# Schematic.net
KiCad netlist of a schematic drawn in Altium Designer
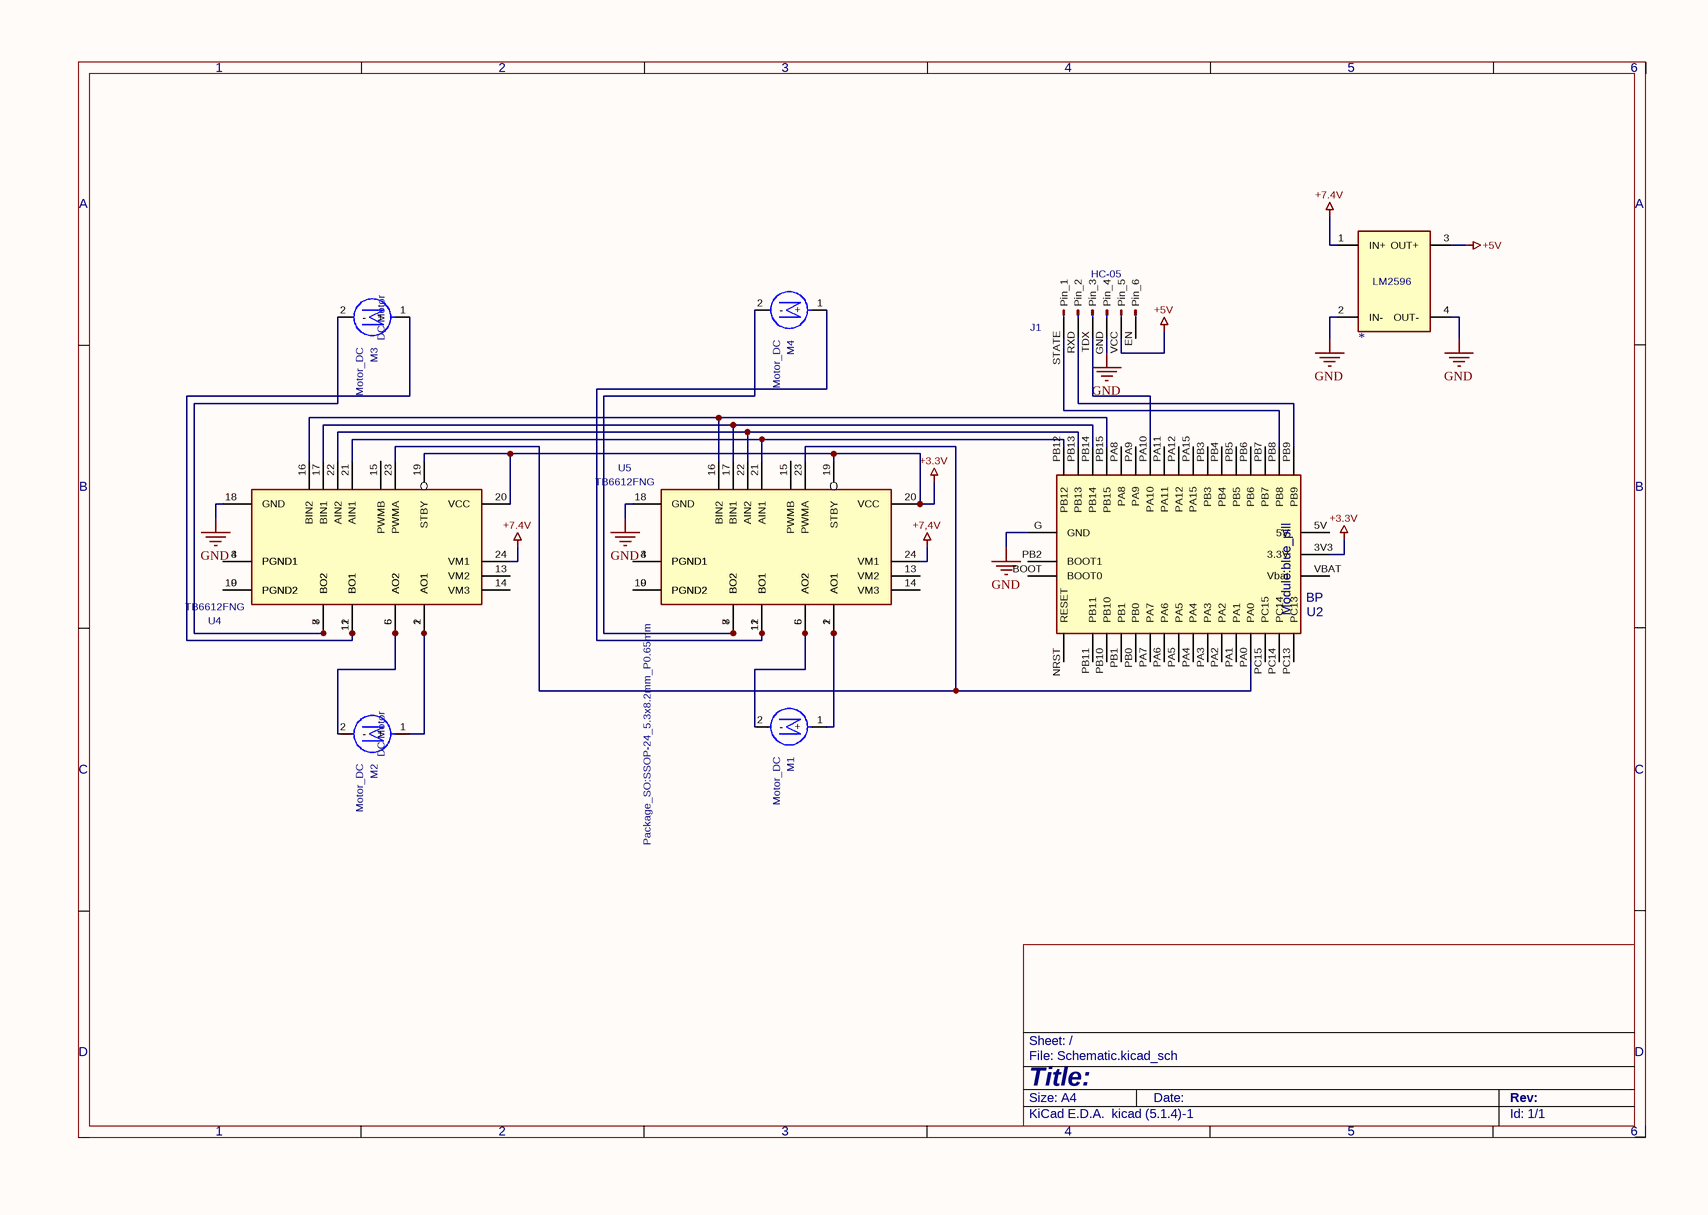
[diagram p0: Schematic.SchDoc]

(export (version "E")
  (design (tool "Eeschema 10.0.6"))
  (components
    (comp (ref "J1") (value "HC-05") (libsource (lib "Connector") (part "Conn_01x06_Pin")))
    (comp (ref "LM2596") (value "*") (libsource (lib "New_Library") (part "LM2596_Module")))
    (comp (ref "M1") (value "Motor_DC") (libsource (lib "Motor") (part "Motor_DC")))
    (comp (ref "M2") (value "Motor_DC") (description "DC Motor") (libsource (lib "Motor") (part "Motor_DC")))
    (comp (ref "M3") (value "Motor_DC") (description "DC Motor") (libsource (lib "Motor") (part "Motor_DC")))
    (comp (ref "M4") (value "Motor_DC") (libsource (lib "Motor") (part "Motor_DC")))
    (comp (ref "U2") (value "BP") (footprint "Module:blue_pill") (libsource (lib "STM32") (part "BP")))
    (comp (ref "U4")
      (value "TB6612FNG")
      (footprint "SSOP-24_5.3x8.2mm_P0.65mm")
      (libsource (lib "Driver_Motor") (part "TB6612FNG"))
    )
    (comp (ref "U5")
      (value "TB6612FNG")
      (footprint "Package_SO:SSOP-24_5.3x8.2mm_P0.65mm")
      (libsource (lib "Driver_Motor") (part "TB6612FNG"))
    )
  )
  (nets
    (net (code "1") (name "+3.3V") (class "Default")
      (node (ref "U2") (pin "3V3") (pinfunction "3.3V_3V3") (pintype "passive"))
      (node (ref "U4") (pin "19") (pinfunction "STBY_19") (pintype "passive"))
      (node (ref "U4") (pin "20") (pinfunction "VCC_20") (pintype "passive"))
      (node (ref "U5") (pin "19") (pinfunction "STBY_19") (pintype "passive"))
      (node (ref "U5") (pin "20") (pinfunction "VCC_20") (pintype "passive"))
    )
    (net (code "2") (name "+5V") (class "Default")
      (node (ref "J1") (pin "VCC") (pinfunction "Pin_5_VCC") (pintype "passive"))
      (node (ref "LM2596") (pin "3") (pinfunction "OUT+_3") (pintype "passive"))
    )
    (net (code "3") (name "+7,4V") (class "Default")
      (node (ref "U5") (pin "24") (pinfunction "VM1_24") (pintype "passive"))
    )
    (net (code "4") (name "+7.4V") (class "Default")
      (node (ref "LM2596") (pin "1") (pinfunction "IN+_1") (pintype "passive"))
      (node (ref "U4") (pin "24") (pinfunction "VM1_24") (pintype "passive"))
    )
    (net (code "5") (name "GND") (class "Default")
      (node (ref "J1") (pin "GND") (pinfunction "Pin_4_GND") (pintype "passive"))
      (node (ref "LM2596") (pin "2") (pinfunction "IN-_2") (pintype "passive"))
      (node (ref "LM2596") (pin "4") (pinfunction "OUT-_4") (pintype "passive"))
      (node (ref "U2") (pin "G") (pinfunction "GND_G") (pintype "passive"))
      (node (ref "U4") (pin "18") (pinfunction "GND_18") (pintype "passive"))
      (node (ref "U5") (pin "18") (pinfunction "GND_18") (pintype "passive"))
    )
    (net (code "6") (name "Net-(J1-Pin_1)") (class "Default")
      (node (ref "J1") (pin "STATE") (pinfunction "Pin_1_STATE") (pintype "passive"))
      (node (ref "U2") (pin "PB8") (pinfunction "PB8_PB8") (pintype "passive"))
    )
    (net (code "7") (name "Net-(J1-Pin_2)") (class "Default")
      (node (ref "J1") (pin "RXD") (pinfunction "Pin_2_RXD") (pintype "passive"))
      (node (ref "U2") (pin "PB9") (pinfunction "PB9_PB9") (pintype "passive"))
    )
    (net (code "8") (name "Net-(J1-Pin_3)") (class "Default")
      (node (ref "J1") (pin "TDX") (pinfunction "Pin_3_TDX") (pintype "passive"))
      (node (ref "U2") (pin "PA10") (pinfunction "PA10_PA10") (pintype "passive"))
    )
    (net (code "9") (name "Net-(M1-+)") (class "Default")
      (node (ref "M1") (pin "1") (pinfunction "+_1") (pintype "passive"))
      (node (ref "U5") (pin "1") (pinfunction "AO1_1") (pintype "passive"))
      (node (ref "U5") (pin "2") (pinfunction "AO1_2") (pintype "passive"))
    )
    (net (code "10") (name "Net-(M1--)") (class "Default")
      (node (ref "M1") (pin "2") (pinfunction "-_2") (pintype "passive"))
      (node (ref "U5") (pin "5") (pinfunction "AO2_5") (pintype "passive"))
      (node (ref "U5") (pin "6") (pinfunction "AO2_6") (pintype "passive"))
    )
    (net (code "11") (name "Net-(M2-+)") (class "Default")
      (node (ref "M2") (pin "1") (pinfunction "+_1") (pintype "passive"))
      (node (ref "U4") (pin "1") (pinfunction "AO1_1") (pintype "passive"))
      (node (ref "U4") (pin "2") (pinfunction "AO1_2") (pintype "passive"))
    )
    (net (code "12") (name "Net-(M2--)") (class "Default")
      (node (ref "M2") (pin "2") (pinfunction "-_2") (pintype "passive"))
      (node (ref "U4") (pin "5") (pinfunction "AO2_5") (pintype "passive"))
      (node (ref "U4") (pin "6") (pinfunction "AO2_6") (pintype "passive"))
    )
    (net (code "13") (name "Net-(M3-+)") (class "Default")
      (node (ref "M3") (pin "1") (pinfunction "+_1") (pintype "passive"))
      (node (ref "U4") (pin "11") (pinfunction "BO1_11") (pintype "passive"))
      (node (ref "U4") (pin "12") (pinfunction "BO1_12") (pintype "passive"))
    )
    (net (code "14") (name "Net-(M3--)") (class "Default")
      (node (ref "M3") (pin "2") (pinfunction "-_2") (pintype "passive"))
      (node (ref "U4") (pin "7") (pinfunction "BO2_7") (pintype "passive"))
      (node (ref "U4") (pin "8") (pinfunction "BO2_8") (pintype "passive"))
    )
    (net (code "15") (name "Net-(M4-+)") (class "Default")
      (node (ref "M4") (pin "1") (pinfunction "+_1") (pintype "passive"))
      (node (ref "U5") (pin "11") (pinfunction "BO1_11") (pintype "passive"))
      (node (ref "U5") (pin "12") (pinfunction "BO1_12") (pintype "passive"))
    )
    (net (code "16") (name "Net-(M4--)") (class "Default")
      (node (ref "M4") (pin "2") (pinfunction "-_2") (pintype "passive"))
      (node (ref "U5") (pin "7") (pinfunction "BO2_7") (pintype "passive"))
      (node (ref "U5") (pin "8") (pinfunction "BO2_8") (pintype "passive"))
    )
    (net (code "17") (name "Net-(U4-AIN1)") (class "Default")
      (node (ref "U2") (pin "PB12") (pinfunction "PB12_PB12") (pintype "passive"))
      (node (ref "U4") (pin "21") (pinfunction "AIN1_21") (pintype "passive"))
      (node (ref "U5") (pin "21") (pinfunction "AIN1_21") (pintype "passive"))
    )
    (net (code "18") (name "Net-(U4-AIN2)") (class "Default")
      (node (ref "U2") (pin "PB13") (pinfunction "PB13_PB13") (pintype "passive"))
      (node (ref "U4") (pin "22") (pinfunction "AIN2_22") (pintype "passive"))
      (node (ref "U5") (pin "22") (pinfunction "AIN2_22") (pintype "passive"))
    )
    (net (code "19") (name "Net-(U4-BIN1)") (class "Default")
      (node (ref "U2") (pin "PB14") (pinfunction "PB14_PB14") (pintype "passive"))
      (node (ref "U4") (pin "17") (pinfunction "BIN1_17") (pintype "passive"))
      (node (ref "U5") (pin "17") (pinfunction "BIN1_17") (pintype "passive"))
    )
    (net (code "20") (name "Net-(U4-BIN2)") (class "Default")
      (node (ref "U2") (pin "PB15") (pinfunction "PB15_PB15") (pintype "passive"))
      (node (ref "U4") (pin "16") (pinfunction "BIN2_16") (pintype "passive"))
      (node (ref "U5") (pin "16") (pinfunction "BIN2_16") (pintype "passive"))
    )
    (net (code "21") (name "Net-(U4-PGND1-Pad3)") (class "Default")
      (node (ref "U4") (pin "3") (pinfunction "PGND1_3") (pintype "passive"))
      (node (ref "U4") (pin "4") (pinfunction "PGND1_4") (pintype "passive"))
    )
    (net (code "22") (name "Net-(U4-PGND2-Pad10)") (class "Default")
      (node (ref "U4") (pin "10") (pinfunction "PGND2_10") (pintype "passive"))
      (node (ref "U4") (pin "9") (pinfunction "PGND2_9") (pintype "passive"))
    )
    (net (code "23") (name "Net-(U4-PWMA)") (class "Default")
      (node (ref "U2") (pin "PA0") (pinfunction "PA0_PA0") (pintype "passive"))
      (node (ref "U4") (pin "23") (pinfunction "PWMA_23") (pintype "passive"))
      (node (ref "U5") (pin "23") (pinfunction "PWMA_23") (pintype "passive"))
    )
    (net (code "24") (name "Net-(U5-PGND1-Pad3)") (class "Default")
      (node (ref "U5") (pin "3") (pinfunction "PGND1_3") (pintype "passive"))
      (node (ref "U5") (pin "4") (pinfunction "PGND1_4") (pintype "passive"))
    )
    (net (code "25") (name "Net-(U5-PGND2-Pad10)") (class "Default")
      (node (ref "U5") (pin "10") (pinfunction "PGND2_10") (pintype "passive"))
      (node (ref "U5") (pin "9") (pinfunction "PGND2_9") (pintype "passive"))
    )
    (net (code "26") (name "unconnected-(J1-Pin_6-PadEN)") (class "Default")
      (node (ref "J1") (pin "EN") (pinfunction "Pin_6_EN") (pintype "passive"))
    )
    (net (code "27") (name "unconnected-(U2-BOOT0-PadBOOT)") (class "Default")
      (node (ref "U2") (pin "BOOT") (pinfunction "BOOT0_BOOT") (pintype "passive"))
    )
    (net (code "28") (name "unconnected-(U2-BOOT1-PadPB2)") (class "Default")
      (node (ref "U2") (pin "PB2") (pinfunction "BOOT1_PB2") (pintype "passive"))
    )
    (net (code "29") (name "unconnected-(U2-Pad5V)") (class "Default")
      (node (ref "U2") (pin "5V") (pinfunction "5V_5V") (pintype "passive"))
    )
    (net (code "30") (name "unconnected-(U2-PadPA1)") (class "Default")
      (node (ref "U2") (pin "PA1") (pinfunction "PA1_PA1") (pintype "passive"))
    )
    (net (code "31") (name "unconnected-(U2-PadPA2)") (class "Default")
      (node (ref "U2") (pin "PA2") (pinfunction "PA2_PA2") (pintype "passive"))
    )
    (net (code "32") (name "unconnected-(U2-PadPA3)") (class "Default")
      (node (ref "U2") (pin "PA3") (pinfunction "PA3_PA3") (pintype "passive"))
    )
    (net (code "33") (name "unconnected-(U2-PadPA4)") (class "Default")
      (node (ref "U2") (pin "PA4") (pinfunction "PA4_PA4") (pintype "passive"))
    )
    (net (code "34") (name "unconnected-(U2-PadPA5)") (class "Default")
      (node (ref "U2") (pin "PA5") (pinfunction "PA5_PA5") (pintype "passive"))
    )
    (net (code "35") (name "unconnected-(U2-PadPA6)") (class "Default")
      (node (ref "U2") (pin "PA6") (pinfunction "PA6_PA6") (pintype "passive"))
    )
    (net (code "36") (name "unconnected-(U2-PadPA7)") (class "Default")
      (node (ref "U2") (pin "PA7") (pinfunction "PA7_PA7") (pintype "passive"))
    )
    (net (code "37") (name "unconnected-(U2-PadPA8)") (class "Default")
      (node (ref "U2") (pin "PA8") (pinfunction "PA8_PA8") (pintype "passive"))
    )
    (net (code "38") (name "unconnected-(U2-PadPA9)") (class "Default")
      (node (ref "U2") (pin "PA9") (pinfunction "PA9_PA9") (pintype "passive"))
    )
    (net (code "39") (name "unconnected-(U2-PadPA11)") (class "Default")
      (node (ref "U2") (pin "PA11") (pinfunction "PA11_PA11") (pintype "passive"))
    )
    (net (code "40") (name "unconnected-(U2-PadPA12)") (class "Default")
      (node (ref "U2") (pin "PA12") (pinfunction "PA12_PA12") (pintype "passive"))
    )
    (net (code "41") (name "unconnected-(U2-PadPA15)") (class "Default")
      (node (ref "U2") (pin "PA15") (pinfunction "PA15_PA15") (pintype "passive"))
    )
    (net (code "42") (name "unconnected-(U2-PadPB0)") (class "Default")
      (node (ref "U2") (pin "PB0") (pinfunction "PB0_PB0") (pintype "passive"))
    )
    (net (code "43") (name "unconnected-(U2-PadPB1)") (class "Default")
      (node (ref "U2") (pin "PB1") (pinfunction "PB1_PB1") (pintype "passive"))
    )
    (net (code "44") (name "unconnected-(U2-PadPB3)") (class "Default")
      (node (ref "U2") (pin "PB3") (pinfunction "PB3_PB3") (pintype "passive"))
    )
    (net (code "45") (name "unconnected-(U2-PadPB4)") (class "Default")
      (node (ref "U2") (pin "PB4") (pinfunction "PB4_PB4") (pintype "passive"))
    )
    (net (code "46") (name "unconnected-(U2-PadPB5)") (class "Default")
      (node (ref "U2") (pin "PB5") (pinfunction "PB5_PB5") (pintype "passive"))
    )
    (net (code "47") (name "unconnected-(U2-PadPB6)") (class "Default")
      (node (ref "U2") (pin "PB6") (pinfunction "PB6_PB6") (pintype "passive"))
    )
    (net (code "48") (name "unconnected-(U2-PadPB7)") (class "Default")
      (node (ref "U2") (pin "PB7") (pinfunction "PB7_PB7") (pintype "passive"))
    )
    (net (code "49") (name "unconnected-(U2-PadPB10)") (class "Default")
      (node (ref "U2") (pin "PB10") (pinfunction "PB10_PB10") (pintype "passive"))
    )
    (net (code "50") (name "unconnected-(U2-PadPB11)") (class "Default")
      (node (ref "U2") (pin "PB11") (pinfunction "PB11_PB11") (pintype "passive"))
    )
    (net (code "51") (name "unconnected-(U2-PadPC13)") (class "Default")
      (node (ref "U2") (pin "PC13") (pinfunction "PC13_PC13") (pintype "passive"))
    )
    (net (code "52") (name "unconnected-(U2-PadPC14)") (class "Default")
      (node (ref "U2") (pin "PC14") (pinfunction "PC14_PC14") (pintype "passive"))
    )
    (net (code "53") (name "unconnected-(U2-PadPC15)") (class "Default")
      (node (ref "U2") (pin "PC15") (pinfunction "PC15_PC15") (pintype "passive"))
    )
    (net (code "54") (name "unconnected-(U2-RESET-PadNRST)") (class "Default")
      (node (ref "U2") (pin "NRST") (pinfunction "RESET_NRST") (pintype "passive"))
    )
    (net (code "55") (name "unconnected-(U2-Vbat-PadVBAT)") (class "Default")
      (node (ref "U2") (pin "VBAT") (pinfunction "Vbat_VBAT") (pintype "passive"))
    )
    (net (code "56") (name "unconnected-(U4-PWMB-Pad15)") (class "Default")
      (node (ref "U4") (pin "15") (pinfunction "PWMB_15") (pintype "passive"))
    )
    (net (code "57") (name "unconnected-(U4-VM2-Pad13)") (class "Default")
      (node (ref "U4") (pin "13") (pinfunction "VM2_13") (pintype "passive"))
    )
    (net (code "58") (name "unconnected-(U4-VM3-Pad14)") (class "Default")
      (node (ref "U4") (pin "14") (pinfunction "VM3_14") (pintype "passive"))
    )
    (net (code "59") (name "unconnected-(U5-PWMB-Pad15)") (class "Default")
      (node (ref "U5") (pin "15") (pinfunction "PWMB_15") (pintype "passive"))
    )
    (net (code "60") (name "unconnected-(U5-VM2-Pad13)") (class "Default")
      (node (ref "U5") (pin "13") (pinfunction "VM2_13") (pintype "passive"))
    )
    (net (code "61") (name "unconnected-(U5-VM3-Pad14)") (class "Default")
      (node (ref "U5") (pin "14") (pinfunction "VM3_14") (pintype "passive"))
    )
  )
)
